# SRAM.net
KiCad netlist of a schematic drawn in Altium Designer
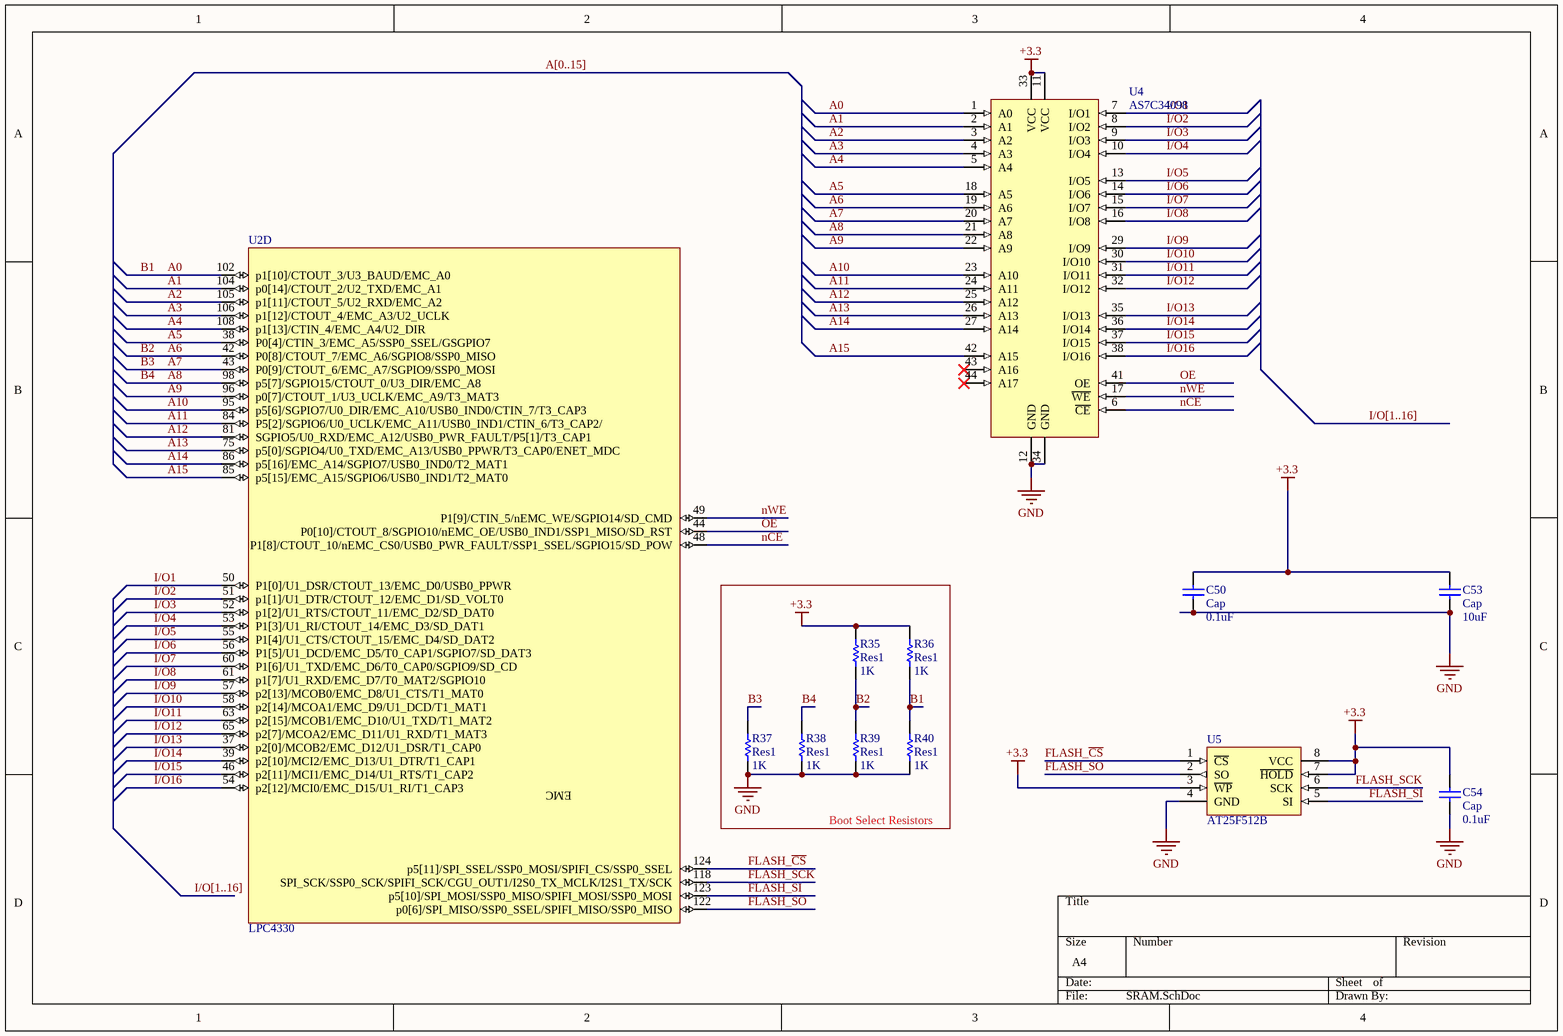
[diagram p0: SRAM.SchDoc]

(export (version "E")
  (design (tool "Eeschema 10.0.6"))
  (components
    (comp (ref "C50")
      (value "Cap")
      (footprint "C0603")
      (description "Capacitor")
      (fields (field (name "ALTIUM_VALUE") "0.1uF") (field (name "PUBLISHER") "Altium Limited"))
      (libsource (lib "Miscellaneous Devices") (part "Cap"))
    )
    (comp (ref "C53")
      (value "Cap")
      (footprint "C0603")
      (description "Capacitor")
      (fields (field (name "ALTIUM_VALUE") "10uF") (field (name "PUBLISHER") "Altium Limited"))
      (libsource (lib "Miscellaneous Devices") (part "Cap"))
    )
    (comp (ref "C54")
      (value "Cap")
      (footprint "C0603")
      (description "Capacitor")
      (fields (field (name "ALTIUM_VALUE") "0.1uF") (field (name "PUBLISHER") "Altium Limited"))
      (libsource (lib "Miscellaneous Devices") (part "Cap"))
    )
    (comp (ref "R35")
      (value "Res1")
      (footprint "R0603")
      (description "Resistor")
      (fields (field (name "ALTIUM_VALUE") "1K") (field (name "PUBLISHER") "Altium Limited"))
      (libsource (lib "Miscellaneous Devices") (part "Res1"))
    )
    (comp (ref "R36")
      (value "Res1")
      (footprint "R0603")
      (description "Resistor")
      (fields (field (name "ALTIUM_VALUE") "1K") (field (name "PUBLISHER") "Altium Limited"))
      (libsource (lib "Miscellaneous Devices") (part "Res1"))
    )
    (comp (ref "R37")
      (value "Res1")
      (footprint "R0603")
      (description "Resistor")
      (fields (field (name "ALTIUM_VALUE") "1K") (field (name "PUBLISHER") "Altium Limited"))
      (libsource (lib "Miscellaneous Devices") (part "Res1"))
    )
    (comp (ref "R38")
      (value "Res1")
      (footprint "R0603")
      (description "Resistor")
      (fields (field (name "ALTIUM_VALUE") "1K") (field (name "PUBLISHER") "Altium Limited"))
      (libsource (lib "Miscellaneous Devices") (part "Res1"))
    )
    (comp (ref "R39")
      (value "Res1")
      (footprint "R0603")
      (description "Resistor")
      (fields (field (name "ALTIUM_VALUE") "1K") (field (name "PUBLISHER") "Altium Limited"))
      (libsource (lib "Miscellaneous Devices") (part "Res1"))
    )
    (comp (ref "R40")
      (value "Res1")
      (footprint "R0603")
      (description "Resistor")
      (fields (field (name "ALTIUM_VALUE") "1K") (field (name "PUBLISHER") "Altium Limited"))
      (libsource (lib "Miscellaneous Devices") (part "Res1"))
    )
    (comp (ref "U2")
      (value "LPC4330")
      (footprint "TSQFP50P2200X2200X160-144N")
      (description "MCU, 32BIT, ARM CORTEX M4&M0, 144LQFP")
      (libsource (lib "LPC4330") (part "LPC4330"))
    )
    (comp (ref "U4")
      (value "AS7C34098")
      (footprint "TSOP80P1180X120-44N")
      (description "SRAM, 4MB, 3V, 12NS, 256K x 16, TSOP44")
      (libsource (lib "AS7C34098") (part "AS7C34098"))
    )
    (comp (ref "U5")
      (value "AT25F512B")
      (footprint "SOIC127P600-8N")
      (description "MEMORY, DATAFLASH, 512K, SPI, 8SOIC")
      (libsource (lib "AT25F512B") (part "AT25F512B"))
    )
  )
  (nets
    (net (code "17") (name "+3.3") (class "Default")
      (node (ref "C50") (pin "2") (pinfunction "2_2") (pintype "passive"))
      (node (ref "C53") (pin "2") (pinfunction "2_2") (pintype "passive"))
      (node (ref "C54") (pin "2") (pinfunction "2_2") (pintype "passive"))
      (node (ref "R35") (pin "2") (pinfunction "2_2") (pintype "passive"))
      (node (ref "R36") (pin "2") (pinfunction "2_2") (pintype "passive"))
      (node (ref "U4") (pin "11") (pinfunction "VCC_11") (pintype "power_in"))
      (node (ref "U4") (pin "33") (pinfunction "VCC_33") (pintype "power_in"))
      (node (ref "U5") (pin "3") (pinfunction "~{WP}_3") (pintype "input"))
      (node (ref "U5") (pin "7") (pinfunction "~{HOLD}_7") (pintype "input"))
      (node (ref "U5") (pin "8") (pinfunction "VCC_8") (pintype "power_in"))
    )
    (net (code "18") (name "/A0") (class "Default")
      (node (ref "R36") (pin "1") (pinfunction "1_1") (pintype "passive"))
      (node (ref "R40") (pin "2") (pinfunction "2_2") (pintype "passive"))
      (node (ref "U2") (pin "102") (pinfunction "p1[10]/CTOUT_3/U3_BAUD/EMC_A0_102") (pintype "bidirectional"))
      (node (ref "U4") (pin "1") (pinfunction "A0_1") (pintype "input"))
    )
    (net (code "19") (name "/A1") (class "Default")
      (node (ref "U2") (pin "104") (pinfunction "p0[14]/CTOUT_2/U2_TXD/EMC_A1_104") (pintype "bidirectional"))
      (node (ref "U4") (pin "2") (pinfunction "A1_2") (pintype "input"))
    )
    (net (code "20") (name "/A2") (class "Default")
      (node (ref "U2") (pin "105") (pinfunction "p1[11]/CTOUT_5/U2_RXD/EMC_A2_105") (pintype "bidirectional"))
      (node (ref "U4") (pin "3") (pinfunction "A2_3") (pintype "input"))
    )
    (net (code "21") (name "/A3") (class "Default")
      (node (ref "U2") (pin "106") (pinfunction "p1[12]/CTOUT_4/EMC_A3/U2_UCLK_106") (pintype "bidirectional"))
      (node (ref "U4") (pin "4") (pinfunction "A3_4") (pintype "input"))
    )
    (net (code "22") (name "/A4") (class "Default")
      (node (ref "U2") (pin "108") (pinfunction "p1[13]/CTIN_4/EMC_A4/U2_DIR_108") (pintype "bidirectional"))
      (node (ref "U4") (pin "5") (pinfunction "A4_5") (pintype "input"))
    )
    (net (code "23") (name "/A5") (class "Default")
      (node (ref "U2") (pin "38") (pinfunction "P0[4]/CTIN_3/EMC_A5/SSP0_SSEL/GSGPIO7_38") (pintype "bidirectional"))
      (node (ref "U4") (pin "18") (pinfunction "A5_18") (pintype "input"))
    )
    (net (code "24") (name "/A6") (class "Default")
      (node (ref "R35") (pin "1") (pinfunction "1_1") (pintype "passive"))
      (node (ref "R39") (pin "2") (pinfunction "2_2") (pintype "passive"))
      (node (ref "U2") (pin "42") (pinfunction "P0[8]/CTOUT_7/EMC_A6/SGPIO8/SSP0_MISO_42") (pintype "bidirectional"))
      (node (ref "U4") (pin "19") (pinfunction "A6_19") (pintype "input"))
    )
    (net (code "25") (name "/A7") (class "Default")
      (node (ref "R37") (pin "2") (pinfunction "2_2") (pintype "passive"))
      (node (ref "U2") (pin "43") (pinfunction "P0[9]/CTOUT_6/EMC_A7/SGPIO9/SSP0_MOSI_43") (pintype "bidirectional"))
      (node (ref "U4") (pin "20") (pinfunction "A7_20") (pintype "input"))
    )
    (net (code "26") (name "/A8") (class "Default")
      (node (ref "R38") (pin "2") (pinfunction "2_2") (pintype "passive"))
      (node (ref "U2") (pin "98") (pinfunction "p5[7]/SGPIO15/CTOUT_0/U3_DIR/EMC_A8_98") (pintype "bidirectional"))
      (node (ref "U4") (pin "21") (pinfunction "A8_21") (pintype "input"))
    )
    (net (code "27") (name "/A9") (class "Default")
      (node (ref "U2") (pin "96") (pinfunction "p0[7]/CTOUT_1/U3_UCLK/EMC_A9/T3_MAT3_96") (pintype "bidirectional"))
      (node (ref "U4") (pin "22") (pinfunction "A9_22") (pintype "input"))
    )
    (net (code "28") (name "/A10") (class "Default")
      (node (ref "U2") (pin "95") (pinfunction "p5[6]/SGPIO7/U0_DIR/EMC_A10/USB0_IND0/CTIN_7/T3_CAP3_95") (pintype "bidirectional"))
      (node (ref "U4") (pin "23") (pinfunction "A10_23") (pintype "input"))
    )
    (net (code "29") (name "/A11") (class "Default")
      (node (ref "U2") (pin "84") (pinfunction "P5[2]/SGPIO6/U0_UCLK/EMC_A11/USB0_IND1/CTIN_6/T3_CAP2/_84") (pintype "bidirectional"))
      (node (ref "U4") (pin "24") (pinfunction "A11_24") (pintype "input"))
    )
    (net (code "30") (name "/A12") (class "Default")
      (node (ref "U2") (pin "81") (pinfunction "SGPIO5/U0_RXD/EMC_A12/USB0_PWR_FAULT/P5[1]/T3_CAP1_81") (pintype "bidirectional"))
      (node (ref "U4") (pin "25") (pinfunction "A12_25") (pintype "input"))
    )
    (net (code "31") (name "/A13") (class "Default")
      (node (ref "U2") (pin "75") (pinfunction "p5[0]/SGPIO4/U0_TXD/EMC_A13/USB0_PPWR/T3_CAP0/ENET_MDC_75") (pintype "bidirectional"))
      (node (ref "U4") (pin "26") (pinfunction "A13_26") (pintype "input"))
    )
    (net (code "32") (name "/A14") (class "Default")
      (node (ref "U2") (pin "86") (pinfunction "p5[16]/EMC_A14/SGPIO7/USB0_IND0/T2_MAT1_86") (pintype "bidirectional"))
      (node (ref "U4") (pin "27") (pinfunction "A14_27") (pintype "input"))
    )
    (net (code "33") (name "/A15") (class "Default")
      (node (ref "U2") (pin "85") (pinfunction "p5[15]/EMC_A15/SGPIO6/USB0_IND1/T2_MAT0_85") (pintype "bidirectional"))
      (node (ref "U4") (pin "42") (pinfunction "A15_42") (pintype "input"))
    )
    (net (code "35") (name "/FLASH_SCK") (class "Default")
      (node (ref "U2") (pin "118") (pinfunction "SPI_SCK/SSP0_SCK/SPIFI_SCK/CGU_OUT1/I2S0_TX_MCLK/I2S1_TX/SCK_118") (pintype "bidirectional"))
      (node (ref "U5") (pin "6") (pinfunction "SCK_6") (pintype "input"))
    )
    (net (code "36") (name "/FLASH_SI") (class "Default")
      (node (ref "U2") (pin "123") (pinfunction "p5[10]/SPI_MOSI/SSP0_MISO/SPIFI_MOSI/SSP0_MOSI_123") (pintype "bidirectional"))
      (node (ref "U5") (pin "5") (pinfunction "SI_5") (pintype "input"))
    )
    (net (code "37") (name "/FLASH_SO") (class "Default")
      (node (ref "U2") (pin "122") (pinfunction "p0[6]/SPI_MISO/SSP0_SSEL/SPIFI_MISO/SSP0_MISO_122") (pintype "bidirectional"))
      (node (ref "U5") (pin "2") (pinfunction "SO_2") (pintype "output"))
    )
    (net (code "38") (name "/FLASH_~{CS}") (class "Default")
      (node (ref "U2") (pin "124") (pinfunction "p5[11]/SPI_SSEL/SSP0_MOSI/SPIFI_CS/SSP0_SSEL_124") (pintype "bidirectional"))
      (node (ref "U5") (pin "1") (pinfunction "~{CS}_1") (pintype "input"))
    )
    (net (code "39") (name "/I{slash}O1") (class "Default")
      (node (ref "U2") (pin "50") (pinfunction "P1[0]/U1_DSR/CTOUT_13/EMC_D0/USB0_PPWR_50") (pintype "bidirectional"))
      (node (ref "U4") (pin "7") (pinfunction "I/O1_7") (pintype "input"))
    )
    (net (code "40") (name "/I{slash}O2") (class "Default")
      (node (ref "U2") (pin "51") (pinfunction "p1[1]/U1_DTR/CTOUT_12/EMC_D1/SD_VOLT0_51") (pintype "bidirectional"))
      (node (ref "U4") (pin "8") (pinfunction "I/O2_8") (pintype "input"))
    )
    (net (code "41") (name "/I{slash}O3") (class "Default")
      (node (ref "U2") (pin "52") (pinfunction "p1[2]/U1_RTS/CTOUT_11/EMC_D2/SD_DAT0_52") (pintype "bidirectional"))
      (node (ref "U4") (pin "9") (pinfunction "I/O3_9") (pintype "input"))
    )
    (net (code "42") (name "/I{slash}O4") (class "Default")
      (node (ref "U2") (pin "53") (pinfunction "P1[3]/U1_RI/CTOUT_14/EMC_D3/SD_DAT1_53") (pintype "bidirectional"))
      (node (ref "U4") (pin "10") (pinfunction "I/O4_10") (pintype "input"))
    )
    (net (code "43") (name "/I{slash}O5") (class "Default")
      (node (ref "U2") (pin "55") (pinfunction "P1[4]/U1_CTS/CTOUT_15/EMC_D4/SD_DAT2_55") (pintype "bidirectional"))
      (node (ref "U4") (pin "13") (pinfunction "I/O5_13") (pintype "input"))
    )
    (net (code "44") (name "/I{slash}O6") (class "Default")
      (node (ref "U2") (pin "56") (pinfunction "P1[5]/U1_DCD/EMC_D5/T0_CAP1/SGPIO7/SD_DAT3_56") (pintype "bidirectional"))
      (node (ref "U4") (pin "14") (pinfunction "I/O6_14") (pintype "input"))
    )
    (net (code "45") (name "/I{slash}O7") (class "Default")
      (node (ref "U2") (pin "60") (pinfunction "P1[6]/U1_TXD/EMC_D6/T0_CAP0/SGPIO9/SD_CD_60") (pintype "bidirectional"))
      (node (ref "U4") (pin "15") (pinfunction "I/O7_15") (pintype "input"))
    )
    (net (code "46") (name "/I{slash}O8") (class "Default")
      (node (ref "U2") (pin "61") (pinfunction "p1[7]/U1_RXD/EMC_D7/T0_MAT2/SGPIO10_61") (pintype "bidirectional"))
      (node (ref "U4") (pin "16") (pinfunction "I/O8_16") (pintype "input"))
    )
    (net (code "47") (name "/I{slash}O9") (class "Default")
      (node (ref "U2") (pin "57") (pinfunction "p2[13]/MCOB0/EMC_D8/U1_CTS/T1_MAT0_57") (pintype "bidirectional"))
      (node (ref "U4") (pin "29") (pinfunction "I/O9_29") (pintype "input"))
    )
    (net (code "48") (name "/I{slash}O10") (class "Default")
      (node (ref "U2") (pin "58") (pinfunction "p2[14]/MCOA1/EMC_D9/U1_DCD/T1_MAT1_58") (pintype "bidirectional"))
      (node (ref "U4") (pin "30") (pinfunction "I/O10_30") (pintype "input"))
    )
    (net (code "49") (name "/I{slash}O11") (class "Default")
      (node (ref "U2") (pin "63") (pinfunction "p2[15]/MCOB1/EMC_D10/U1_TXD/T1_MAT2_63") (pintype "bidirectional"))
      (node (ref "U4") (pin "31") (pinfunction "I/O11_31") (pintype "input"))
    )
    (net (code "50") (name "/I{slash}O12") (class "Default")
      (node (ref "U2") (pin "65") (pinfunction "p2[7]/MCOA2/EMC_D11/U1_RXD/T1_MAT3_65") (pintype "bidirectional"))
      (node (ref "U4") (pin "32") (pinfunction "I/O12_32") (pintype "input"))
    )
    (net (code "51") (name "/I{slash}O13") (class "Default")
      (node (ref "U2") (pin "37") (pinfunction "p2[0]/MCOB2/EMC_D12/U1_DSR/T1_CAP0_37") (pintype "bidirectional"))
      (node (ref "U4") (pin "35") (pinfunction "I/O13_35") (pintype "input"))
    )
    (net (code "52") (name "/I{slash}O14") (class "Default")
      (node (ref "U2") (pin "39") (pinfunction "p2[10]/MCI2/EMC_D13/U1_DTR/T1_CAP1_39") (pintype "bidirectional"))
      (node (ref "U4") (pin "36") (pinfunction "I/O14_36") (pintype "input"))
    )
    (net (code "53") (name "/I{slash}O15") (class "Default")
      (node (ref "U2") (pin "46") (pinfunction "p2[11]/MCI1/EMC_D14/U1_RTS/T1_CAP2_46") (pintype "bidirectional"))
      (node (ref "U4") (pin "37") (pinfunction "I/O15_37") (pintype "input"))
    )
    (net (code "54") (name "/I{slash}O16") (class "Default")
      (node (ref "U2") (pin "54") (pinfunction "p2[12]/MCI0/EMC_D15/U1_RI/T1_CAP3_54") (pintype "bidirectional"))
      (node (ref "U4") (pin "38") (pinfunction "I/O16_38") (pintype "input"))
    )
    (net (code "56") (name "/OE") (class "Default")
      (node (ref "U2") (pin "44") (pinfunction "P0[10]/CTOUT_8/SGPIO10/nEMC_OE/USB0_IND1/SSP1_MISO/SD_RST_44") (pintype "bidirectional"))
      (node (ref "U4") (pin "41") (pinfunction "OE_41") (pintype "input"))
    )
    (net (code "57") (name "/nCE") (class "Default")
      (node (ref "U2") (pin "48") (pinfunction "P1[8]/CTOUT_10/nEMC_CS0/USB0_PWR_FAULT/SSP1_SSEL/SGPIO15/SD_POW_48") (pintype "bidirectional"))
      (node (ref "U4") (pin "6") (pinfunction "~{CE}_6") (pintype "input"))
    )
    (net (code "58") (name "/nWE") (class "Default")
      (node (ref "U2") (pin "49") (pinfunction "P1[9]/CTIN_5/nEMC_WE/SGPIO14/SD_CMD_49") (pintype "bidirectional"))
      (node (ref "U4") (pin "17") (pinfunction "~{WE}_17") (pintype "input"))
    )
    (net (code "59") (name "GND") (class "Default")
      (node (ref "C50") (pin "1") (pinfunction "1_1") (pintype "passive"))
      (node (ref "C53") (pin "1") (pinfunction "1_1") (pintype "passive"))
      (node (ref "C54") (pin "1") (pinfunction "1_1") (pintype "passive"))
      (node (ref "R37") (pin "1") (pinfunction "1_1") (pintype "passive"))
      (node (ref "R38") (pin "1") (pinfunction "1_1") (pintype "passive"))
      (node (ref "R39") (pin "1") (pinfunction "1_1") (pintype "passive"))
      (node (ref "R40") (pin "1") (pinfunction "1_1") (pintype "passive"))
      (node (ref "U4") (pin "12") (pinfunction "GND_12") (pintype "power_in"))
      (node (ref "U4") (pin "34") (pinfunction "GND_34") (pintype "power_in"))
      (node (ref "U5") (pin "4") (pinfunction "GND_4") (pintype "power_in"))
    )
    (net (code "60") (name "unconnected-(U4-A16-Pad43)") (class "Default")
      (node (ref "U4") (pin "43") (pinfunction "A16_43") (pintype "input+no_connect"))
    )
    (net (code "61") (name "unconnected-(U4-A17-Pad44)") (class "Default")
      (node (ref "U4") (pin "44") (pinfunction "A17_44") (pintype "input+no_connect"))
    )
  )
)
